# main.net
KiCad netlist of a schematic drawn in EAGLE
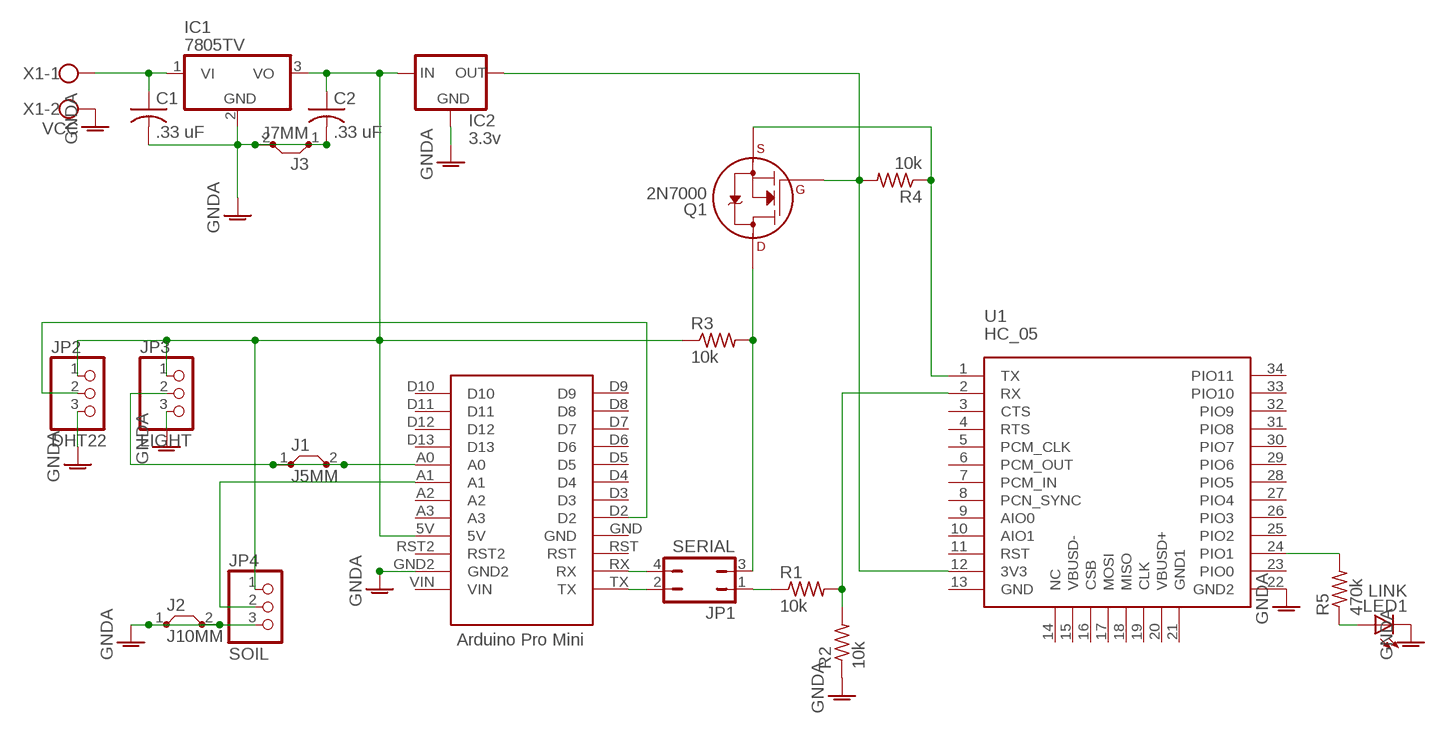
[diagram p0: schematic, sheet 1]

(export (version "E")
  (design (tool "Eeschema 10.0.6"))
  (components
    (comp (ref "C1")
      (value ".33 uF")
      (footprint "eagle-import:C025-050X050")
      (libsource (lib "eagle-import") (part "C-US025-050X050"))
    )
    (comp (ref "C2")
      (value ".33 uF")
      (footprint "eagle-import:C025-050X050")
      (libsource (lib "eagle-import") (part "C-US025-050X050"))
    )
    (comp (ref "IC1")
      (value "7805TV")
      (footprint "eagle-import:TO220V")
      (libsource (lib "eagle-import") (part "78TV05"))
    )
    (comp (ref "IC2")
      (value "3.3v")
      (footprint "eagle-import:TO92-INLINE")
      (libsource (lib "eagle-import") (part "MCP1700INLINE"))
    )
    (comp (ref "J1")
      (value "J5MM")
      (footprint "eagle-import:05")
      (libsource (lib "eagle-import") (part "J5MM"))
    )
    (comp (ref "J2")
      (value "J10MM")
      (footprint "eagle-import:10")
      (libsource (lib "eagle-import") (part "J10MM"))
    )
    (comp (ref "J3")
      (value "J7MM")
      (footprint "eagle-import:07")
      (libsource (lib "eagle-import") (part "J7MM"))
    )
    (comp (ref "JP1")
      (value "SERIAL")
      (footprint "eagle-import:JP2Q")
      (libsource (lib "eagle-import") (part "JP2Q"))
    )
    (comp (ref "JP2")
      (value "DHT22")
      (footprint "eagle-import:1X03")
      (libsource (lib "eagle-import") (part "PINHD-1X3"))
    )
    (comp (ref "JP3")
      (value "LIGHT")
      (footprint "eagle-import:1X03")
      (libsource (lib "eagle-import") (part "PINHD-1X3"))
    )
    (comp (ref "JP4")
      (value "SOIL")
      (footprint "eagle-import:1X03")
      (libsource (lib "eagle-import") (part "PINHD-1X3"))
    )
    (comp (ref "LED1")
      (value "LINK")
      (footprint "eagle-import:LED3MM")
      (libsource (lib "eagle-import") (part "LED3MM"))
    )
    (comp (ref "Q1")
      (value "2N7000")
      (footprint "eagle-import:TO-92")
      (libsource (lib "eagle-import") (part "2N700_TO920"))
    )
    (comp (ref "R1")
      (value "10k")
      (footprint "eagle-import:0204_7")
      (libsource (lib "eagle-import") (part "R-US_0204/7"))
    )
    (comp (ref "R2")
      (value "10k")
      (footprint "eagle-import:0204_7")
      (libsource (lib "eagle-import") (part "R-US_0204/7"))
    )
    (comp (ref "R3")
      (value "10k")
      (footprint "eagle-import:0204_7")
      (libsource (lib "eagle-import") (part "R-US_0204/7"))
    )
    (comp (ref "R4")
      (value "10k")
      (footprint "eagle-import:0204_7")
      (libsource (lib "eagle-import") (part "R-US_0204/7"))
    )
    (comp (ref "R5")
      (value "470k")
      (footprint "eagle-import:0204_7")
      (libsource (lib "eagle-import") (part "R-US_0204/7"))
    )
    (comp (ref "U$1")
      (value "ARDUINO_PRO_MINI_5V_V1V1")
      (footprint "eagle-import:ARDUINO_PRO_MINI_5V_V1")
      (libsource (lib "eagle-import") (part "ARDUINO_PRO_MINI_5V_V1V1"))
    )
    (comp (ref "U1")
      (value "HC_05")
      (footprint "eagle-import:BLUETOOTH_SMD")
      (libsource (lib "eagle-import") (part "HC_05"))
    )
    (comp (ref "X1")
      (value "VCC")
      (footprint "eagle-import:W237-102")
      (fields (field (name "MPN") "237-102"))
      (libsource (lib "eagle-import") (part "W237-102"))
    )
  )
  (nets
    (net (code "1") (name "GNDA") (class "Default")
      (node (ref "C1") (pin "2") (pinfunction "2_2") (pintype "passive"))
      (node (ref "C2") (pin "2") (pinfunction "2_2") (pintype "passive"))
      (node (ref "IC1") (pin "2") (pinfunction "GND_2") (pintype "passive"))
      (node (ref "IC2") (pin "1") (pinfunction "GND_1") (pintype "input"))
      (node (ref "J2") (pin "1") (pinfunction "1_1") (pintype "passive"))
      (node (ref "J2") (pin "2") (pinfunction "2_2") (pintype "passive"))
      (node (ref "J3") (pin "1") (pinfunction "1_1") (pintype "passive"))
      (node (ref "J3") (pin "2") (pinfunction "2_2") (pintype "passive"))
      (node (ref "JP2") (pin "3") (pinfunction "3_3") (pintype "passive"))
      (node (ref "JP3") (pin "3") (pinfunction "3_3") (pintype "passive"))
      (node (ref "JP4") (pin "3") (pinfunction "3_3") (pintype "passive"))
      (node (ref "LED1") (pin "K") (pinfunction "C_K") (pintype "passive"))
      (node (ref "R2") (pin "1") (pinfunction "1_1") (pintype "passive"))
      (node (ref "U$1") (pin "GND2") (pinfunction "GND2_GND2") (pintype "bidirectional"))
      (node (ref "U1") (pin "22") (pinfunction "GND2_22") (pintype "bidirectional"))
      (node (ref "X1") (pin "2") (pinfunction "KL_2") (pintype "passive"))
    )
    (net (code "2") (name "Net-(IC1-VI)") (class "Default")
      (node (ref "C1") (pin "1") (pinfunction "1_1") (pintype "passive"))
      (node (ref "IC1") (pin "1") (pinfunction "VI_1") (pintype "input"))
      (node (ref "X1") (pin "1") (pinfunction "KL_1") (pintype "passive"))
    )
    (net (code "3") (name "Net-(IC1-VO)") (class "Default")
      (node (ref "C2") (pin "1") (pinfunction "1_1") (pintype "passive"))
      (node (ref "IC1") (pin "3") (pinfunction "VO_3") (pintype "passive"))
      (node (ref "IC2") (pin "2") (pinfunction "IN_2") (pintype "input"))
      (node (ref "JP2") (pin "1") (pinfunction "1_1") (pintype "passive"))
      (node (ref "JP3") (pin "1") (pinfunction "1_1") (pintype "passive"))
      (node (ref "JP4") (pin "1") (pinfunction "1_1") (pintype "passive"))
      (node (ref "R3") (pin "1") (pinfunction "1_1") (pintype "passive"))
      (node (ref "U$1") (pin "5V") (pinfunction "5V_5V") (pintype "bidirectional"))
    )
    (net (code "4") (name "Net-(IC2-OUT)") (class "Default")
      (node (ref "IC2") (pin "3") (pinfunction "OUT_3") (pintype "passive"))
      (node (ref "Q1") (pin "2") (pinfunction "G_2") (pintype "tri_state"))
      (node (ref "R4") (pin "2") (pinfunction "2_2") (pintype "passive"))
      (node (ref "U1") (pin "12") (pinfunction "3V3_12") (pintype "bidirectional"))
    )
    (net (code "5") (name "Net-(J1-Pad1)") (class "Default")
      (node (ref "J1") (pin "1") (pinfunction "1_1") (pintype "passive"))
      (node (ref "J1") (pin "2") (pinfunction "2_2") (pintype "passive"))
      (node (ref "JP3") (pin "2") (pinfunction "2_2") (pintype "passive"))
      (node (ref "U$1") (pin "A0") (pinfunction "A0_A0") (pintype "bidirectional"))
    )
    (net (code "6") (name "Net-(JP1-Pad1)") (class "Default")
      (node (ref "JP1") (pin "1") (pinfunction "1_1") (pintype "passive"))
      (node (ref "R1") (pin "1") (pinfunction "1_1") (pintype "passive"))
    )
    (net (code "7") (name "Net-(JP1-Pad2)") (class "Default")
      (node (ref "JP1") (pin "2") (pinfunction "2_2") (pintype "passive"))
      (node (ref "U$1") (pin "TX") (pinfunction "TX_TX") (pintype "bidirectional"))
    )
    (net (code "8") (name "Net-(JP1-Pad4)") (class "Default")
      (node (ref "JP1") (pin "4") (pinfunction "4_4") (pintype "passive"))
      (node (ref "U$1") (pin "RX") (pinfunction "RX_RX") (pintype "bidirectional"))
    )
    (net (code "9") (name "Net-(JP2-Pad2)") (class "Default")
      (node (ref "JP2") (pin "2") (pinfunction "2_2") (pintype "passive"))
      (node (ref "U$1") (pin "D2") (pinfunction "D2_D2") (pintype "bidirectional"))
    )
    (net (code "10") (name "Net-(JP4-Pad2)") (class "Default")
      (node (ref "JP4") (pin "2") (pinfunction "2_2") (pintype "passive"))
      (node (ref "U$1") (pin "A1") (pinfunction "A1_A1") (pintype "bidirectional"))
    )
    (net (code "11") (name "Net-(LED1-PadA)") (class "Default")
      (node (ref "LED1") (pin "A") (pinfunction "A_A") (pintype "passive"))
      (node (ref "R5") (pin "1") (pinfunction "1_1") (pintype "passive"))
    )
    (net (code "12") (name "Net-(Q1-D)") (class "Default")
      (node (ref "JP1") (pin "3") (pinfunction "3_3") (pintype "passive"))
      (node (ref "Q1") (pin "3") (pinfunction "D_3") (pintype "bidirectional"))
      (node (ref "R3") (pin "2") (pinfunction "2_2") (pintype "passive"))
    )
    (net (code "13") (name "Net-(Q1-S)") (class "Default")
      (node (ref "Q1") (pin "1") (pinfunction "S_1") (pintype "bidirectional"))
      (node (ref "R4") (pin "1") (pinfunction "1_1") (pintype "passive"))
      (node (ref "U1") (pin "1") (pinfunction "TX_1") (pintype "bidirectional"))
    )
    (net (code "14") (name "Net-(U1-PIO1)") (class "Default")
      (node (ref "R5") (pin "2") (pinfunction "2_2") (pintype "passive"))
      (node (ref "U1") (pin "24") (pinfunction "PIO1_24") (pintype "bidirectional"))
    )
    (net (code "15") (name "Net-(U1-RX)") (class "Default")
      (node (ref "R1") (pin "2") (pinfunction "2_2") (pintype "passive"))
      (node (ref "R2") (pin "2") (pinfunction "2_2") (pintype "passive"))
      (node (ref "U1") (pin "2") (pinfunction "RX_2") (pintype "bidirectional"))
    )
    (net (code "16") (name "unconnected-(U$1-PadA2)") (class "Default")
      (node (ref "U$1") (pin "A2") (pinfunction "A2_A2") (pintype "bidirectional"))
    )
    (net (code "17") (name "unconnected-(U$1-PadA3)") (class "Default")
      (node (ref "U$1") (pin "A3") (pinfunction "A3_A3") (pintype "bidirectional"))
    )
    (net (code "18") (name "unconnected-(U$1-PadD3)") (class "Default")
      (node (ref "U$1") (pin "D3") (pinfunction "D3_D3") (pintype "bidirectional"))
    )
    (net (code "19") (name "unconnected-(U$1-PadD4)") (class "Default")
      (node (ref "U$1") (pin "D4") (pinfunction "D4_D4") (pintype "bidirectional"))
    )
    (net (code "20") (name "unconnected-(U$1-PadD5)") (class "Default")
      (node (ref "U$1") (pin "D5") (pinfunction "D5_D5") (pintype "bidirectional"))
    )
    (net (code "21") (name "unconnected-(U$1-PadD6)") (class "Default")
      (node (ref "U$1") (pin "D6") (pinfunction "D6_D6") (pintype "bidirectional"))
    )
    (net (code "22") (name "unconnected-(U$1-PadD7)") (class "Default")
      (node (ref "U$1") (pin "D7") (pinfunction "D7_D7") (pintype "bidirectional"))
    )
    (net (code "23") (name "unconnected-(U$1-PadD8)") (class "Default")
      (node (ref "U$1") (pin "D8") (pinfunction "D8_D8") (pintype "bidirectional"))
    )
    (net (code "24") (name "unconnected-(U$1-PadD9)") (class "Default")
      (node (ref "U$1") (pin "D9") (pinfunction "D9_D9") (pintype "bidirectional"))
    )
    (net (code "25") (name "unconnected-(U$1-PadD10)") (class "Default")
      (node (ref "U$1") (pin "D10") (pinfunction "D10_D10") (pintype "bidirectional"))
    )
    (net (code "26") (name "unconnected-(U$1-PadD11)") (class "Default")
      (node (ref "U$1") (pin "D11") (pinfunction "D11_D11") (pintype "bidirectional"))
    )
    (net (code "27") (name "unconnected-(U$1-PadD12)") (class "Default")
      (node (ref "U$1") (pin "D12") (pinfunction "D12_D12") (pintype "bidirectional"))
    )
    (net (code "28") (name "unconnected-(U$1-PadD13)") (class "Default")
      (node (ref "U$1") (pin "D13") (pinfunction "D13_D13") (pintype "bidirectional"))
    )
    (net (code "29") (name "unconnected-(U$1-PadGND)") (class "Default")
      (node (ref "U$1") (pin "GND") (pinfunction "GND_GND") (pintype "bidirectional"))
    )
    (net (code "30") (name "unconnected-(U$1-PadRST)") (class "Default")
      (node (ref "U$1") (pin "RST") (pinfunction "RST_RST") (pintype "bidirectional"))
    )
    (net (code "31") (name "unconnected-(U$1-PadRST2)") (class "Default")
      (node (ref "U$1") (pin "RST2") (pinfunction "RST2_RST2") (pintype "bidirectional"))
    )
    (net (code "32") (name "unconnected-(U$1-PadVIN)") (class "Default")
      (node (ref "U$1") (pin "VIN") (pinfunction "VIN_VIN") (pintype "bidirectional"))
    )
    (net (code "33") (name "unconnected-(U1-AIO0-Pad9)") (class "Default")
      (node (ref "U1") (pin "9") (pinfunction "AIO0_9") (pintype "bidirectional"))
    )
    (net (code "34") (name "unconnected-(U1-AIO1-Pad10)") (class "Default")
      (node (ref "U1") (pin "10") (pinfunction "AIO1_10") (pintype "bidirectional"))
    )
    (net (code "35") (name "unconnected-(U1-CLK-Pad19)") (class "Default")
      (node (ref "U1") (pin "19") (pinfunction "CLK_19") (pintype "bidirectional"))
    )
    (net (code "36") (name "unconnected-(U1-CSB-Pad16)") (class "Default")
      (node (ref "U1") (pin "16") (pinfunction "CSB_16") (pintype "bidirectional"))
    )
    (net (code "37") (name "unconnected-(U1-CTS-Pad3)") (class "Default")
      (node (ref "U1") (pin "3") (pinfunction "CTS_3") (pintype "bidirectional"))
    )
    (net (code "38") (name "unconnected-(U1-GND-Pad13)") (class "Default")
      (node (ref "U1") (pin "13") (pinfunction "GND_13") (pintype "bidirectional"))
    )
    (net (code "39") (name "unconnected-(U1-GND1-Pad21)") (class "Default")
      (node (ref "U1") (pin "21") (pinfunction "GND1_21") (pintype "bidirectional"))
    )
    (net (code "40") (name "unconnected-(U1-MISO-Pad18)") (class "Default")
      (node (ref "U1") (pin "18") (pinfunction "MISO_18") (pintype "bidirectional"))
    )
    (net (code "41") (name "unconnected-(U1-MOSI-Pad17)") (class "Default")
      (node (ref "U1") (pin "17") (pinfunction "MOSI_17") (pintype "bidirectional"))
    )
    (net (code "42") (name "unconnected-(U1-NC-Pad14)") (class "Default")
      (node (ref "U1") (pin "14") (pinfunction "NC_14") (pintype "bidirectional"))
    )
    (net (code "43") (name "unconnected-(U1-PCM_CLK-Pad5)") (class "Default")
      (node (ref "U1") (pin "5") (pinfunction "PCM_CLK_5") (pintype "bidirectional"))
    )
    (net (code "44") (name "unconnected-(U1-PCM_IN-Pad7)") (class "Default")
      (node (ref "U1") (pin "7") (pinfunction "PCM_IN_7") (pintype "bidirectional"))
    )
    (net (code "45") (name "unconnected-(U1-PCM_OUT-Pad6)") (class "Default")
      (node (ref "U1") (pin "6") (pinfunction "PCM_OUT_6") (pintype "bidirectional"))
    )
    (net (code "46") (name "unconnected-(U1-PCN_SYNC-Pad8)") (class "Default")
      (node (ref "U1") (pin "8") (pinfunction "PCN_SYNC_8") (pintype "bidirectional"))
    )
    (net (code "47") (name "unconnected-(U1-PIO0-Pad23)") (class "Default")
      (node (ref "U1") (pin "23") (pinfunction "PIO0_23") (pintype "bidirectional"))
    )
    (net (code "48") (name "unconnected-(U1-PIO2-Pad25)") (class "Default")
      (node (ref "U1") (pin "25") (pinfunction "PIO2_25") (pintype "bidirectional"))
    )
    (net (code "49") (name "unconnected-(U1-PIO3-Pad26)") (class "Default")
      (node (ref "U1") (pin "26") (pinfunction "PIO3_26") (pintype "bidirectional"))
    )
    (net (code "50") (name "unconnected-(U1-PIO4-Pad27)") (class "Default")
      (node (ref "U1") (pin "27") (pinfunction "PIO4_27") (pintype "bidirectional"))
    )
    (net (code "51") (name "unconnected-(U1-PIO5-Pad28)") (class "Default")
      (node (ref "U1") (pin "28") (pinfunction "PIO5_28") (pintype "bidirectional"))
    )
    (net (code "52") (name "unconnected-(U1-PIO6-Pad29)") (class "Default")
      (node (ref "U1") (pin "29") (pinfunction "PIO6_29") (pintype "bidirectional"))
    )
    (net (code "53") (name "unconnected-(U1-PIO7-Pad30)") (class "Default")
      (node (ref "U1") (pin "30") (pinfunction "PIO7_30") (pintype "bidirectional"))
    )
    (net (code "54") (name "unconnected-(U1-PIO8-Pad31)") (class "Default")
      (node (ref "U1") (pin "31") (pinfunction "PIO8_31") (pintype "bidirectional"))
    )
    (net (code "55") (name "unconnected-(U1-PIO9-Pad32)") (class "Default")
      (node (ref "U1") (pin "32") (pinfunction "PIO9_32") (pintype "bidirectional"))
    )
    (net (code "56") (name "unconnected-(U1-PIO10-Pad33)") (class "Default")
      (node (ref "U1") (pin "33") (pinfunction "PIO10_33") (pintype "bidirectional"))
    )
    (net (code "57") (name "unconnected-(U1-PIO11-Pad34)") (class "Default")
      (node (ref "U1") (pin "34") (pinfunction "PIO11_34") (pintype "bidirectional"))
    )
    (net (code "58") (name "unconnected-(U1-RST-Pad11)") (class "Default")
      (node (ref "U1") (pin "11") (pinfunction "RST_11") (pintype "bidirectional"))
    )
    (net (code "59") (name "unconnected-(U1-RTS-Pad4)") (class "Default")
      (node (ref "U1") (pin "4") (pinfunction "RTS_4") (pintype "bidirectional"))
    )
    (net (code "60") (name "unconnected-(U1-VBUSD+-Pad20)") (class "Default")
      (node (ref "U1") (pin "20") (pinfunction "VBUSD+_20") (pintype "bidirectional"))
    )
    (net (code "61") (name "unconnected-(U1-VBUSD--Pad15)") (class "Default")
      (node (ref "U1") (pin "15") (pinfunction "VBUSD-_15") (pintype "bidirectional"))
    )
  )
)
